# 4_IMU.net
KiCad netlist of a schematic drawn in Altium Designer
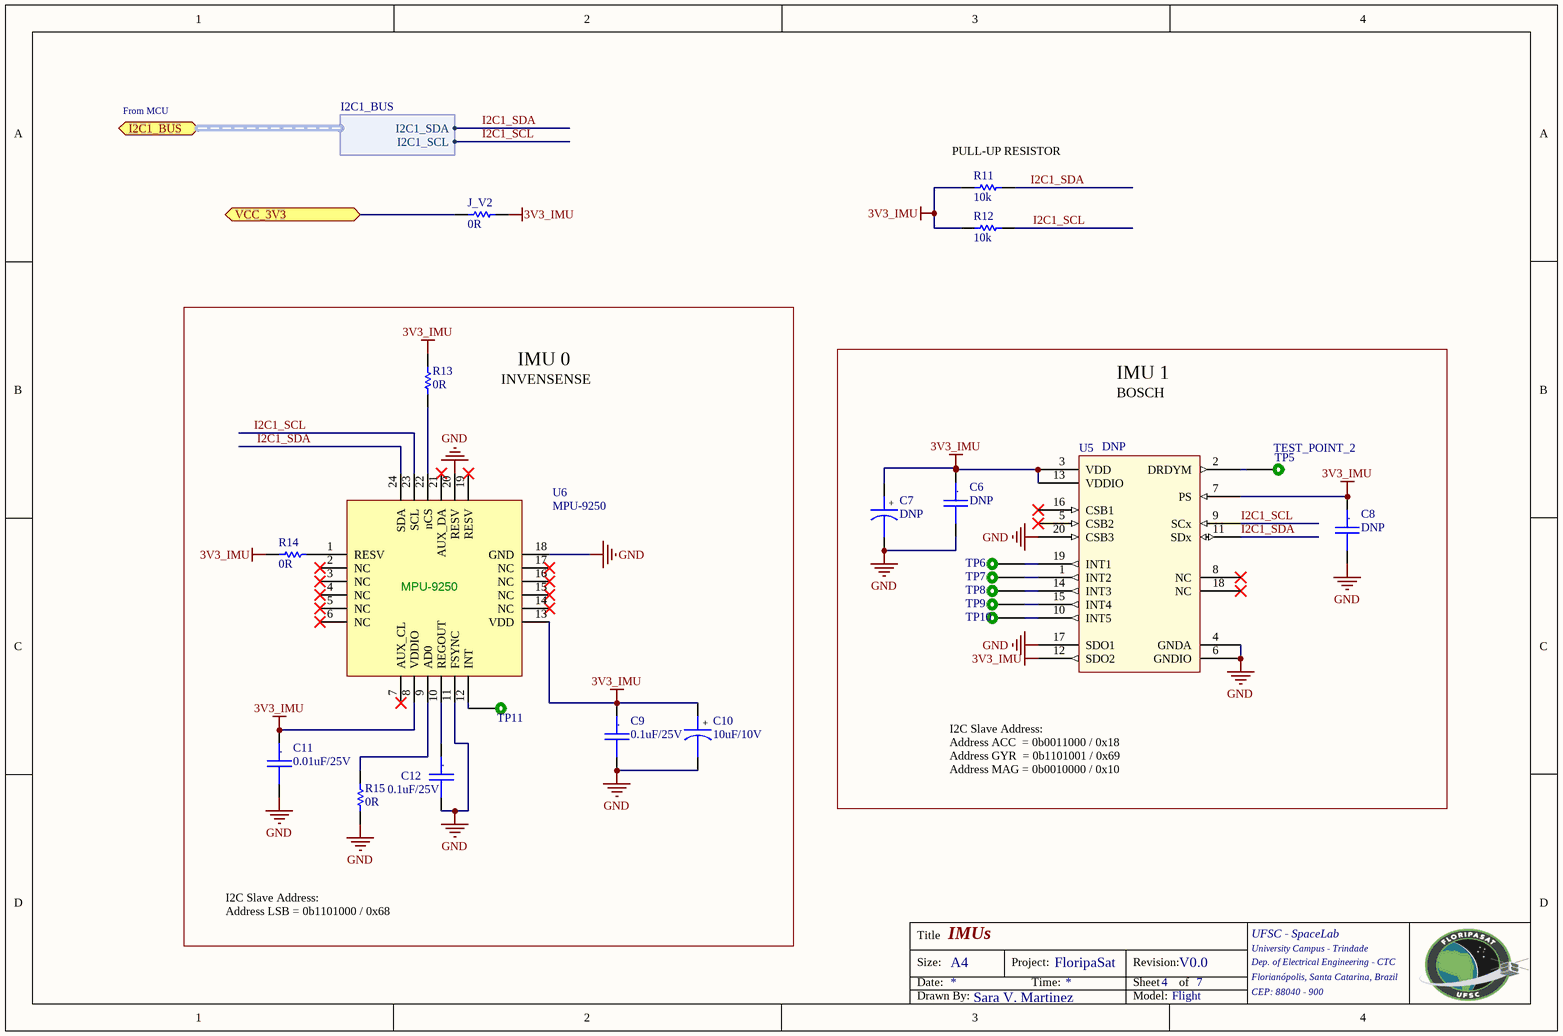
[diagram p0: 4_IMU.SchDoc]

(export (version "E")
  (design (tool "Eeschema 10.0.6"))
  (components
    (comp (ref "C6")
      (value "DNP")
      (footprint "CC0805")
      (description "CAP CER 0.1UF 25V 10% X7R 0805")
      (fields (field (name "PARTNUMBER") "CC0805KRX7R8BB104"))
      (libsource (lib "FloripaSatSchlib") (part "Cap_Cer_X7R_0.1uF_25V_0805"))
    )
    (comp (ref "C7")
      (value "DNP")
      (footprint "FloripaSatPcbLib:CC0805_Tantalum")
      (description "CAP Tantalum 10uF 10V 20% 0805")
      (fields (field (name "PARTNUMBER") "TPSP106M010R2000"))
      (libsource (lib "FloripaSatSchlib") (part "Cap_Tant_SMD_10uF_10V_0805"))
    )
    (comp (ref "C8")
      (value "DNP")
      (footprint "CC0805")
      (description "CAP CER 0.1UF 25V 10% X7R 0805")
      (fields (field (name "PARTNUMBER") "CC0805KRX7R8BB104"))
      (libsource (lib "FloripaSatSchlib") (part "Cap_Cer_X7R_0.1uF_25V_0805"))
    )
    (comp (ref "C9")
      (value "0.1uF/25V")
      (footprint "CC0805")
      (description "CAP CER 0.1UF 25V 10% X7R 0805")
      (fields (field (name "PARTNUMBER") "CC0805KRX7R8BB104"))
      (libsource (lib "FloripaSatSchlib") (part "Cap_Cer_X7R_0.1uF_25V_0805"))
    )
    (comp (ref "C10")
      (value "10uF/10V")
      (footprint "FloripaSatPcbLib:CC0805_Tantalum")
      (description "CAP Tantalum 10uF 10V 20% 0805")
      (fields (field (name "PARTNUMBER") "TPSP106M010R2000"))
      (libsource (lib "FloripaSatSchlib") (part "Cap_Tant_SMD_10uF_10V_0805"))
    )
    (comp (ref "C11")
      (value "0.01uF/25V")
      (footprint "CC0805")
      (description "CAP CER 0.01uF 25V 10% X7R 0805")
      (fields (field (name "PARTNUMBER") "CL21B103KAANNNC"))
      (libsource (lib "FloripaSatSchlib") (part "Cap_Cer_X7R_0.01uF_50V_0805"))
    )
    (comp (ref "C12")
      (value "0.1uF/25V")
      (footprint "CC0805")
      (description "CAP CER 0.1UF 25V 10% X7R 0805")
      (fields (field (name "PARTNUMBER") "CC0805KRX7R8BB104"))
      (libsource (lib "FloripaSatSchlib") (part "Cap_Cer_X7R_0.1uF_25V_0805"))
    )
    (comp (ref "J_V2")
      (value "0R")
      (footprint "FloripaSatPcbLib:0805")
      (description "RES 0R OHM 1/16W JUMPER 0805")
      (fields (field (name "PARTNUMBER") "CRCW08050000Z0EA"))
      (libsource (lib "FloripaSatSchlib") (part "R0R_JUMPER_1/16W_0805"))
    )
    (comp (ref "R11")
      (value "10k")
      (footprint "0805")
      (description "RES 10K OHM 1/8W 1%  0805")
      (fields (field (name "PARTNUMBER") "CRCW080510K0FKEA"))
      (libsource (lib "FloripaSatSchlib") (part "R10k_1%_1/8W_0805"))
    )
    (comp (ref "R12")
      (value "10k")
      (footprint "0805")
      (description "RES 10K OHM 1/8W 1%  0805")
      (fields (field (name "PARTNUMBER") "CRCW080510K0FKEA"))
      (libsource (lib "FloripaSatSchlib") (part "R10k_1%_1/8W_0805"))
    )
    (comp (ref "R13")
      (value "0R")
      (footprint "FloripaSatPcbLib:0805")
      (description "RES 0R OHM 1/16W JUMPER 0805")
      (fields (field (name "PARTNUMBER") "CRCW08050000Z0EA"))
      (libsource (lib "FloripaSatSchlib") (part "R0R_JUMPER_1/16W_0805"))
    )
    (comp (ref "R14")
      (value "0R")
      (footprint "FloripaSatPcbLib:0805")
      (description "RES 0R OHM 1/16W JUMPER 0805")
      (fields (field (name "PARTNUMBER") "CRCW08050000Z0EA"))
      (libsource (lib "FloripaSatSchlib") (part "R0R_JUMPER_1/16W_0805"))
    )
    (comp (ref "R15")
      (value "0R")
      (footprint "FloripaSatPcbLib:0805")
      (description "RES 0R OHM 1/16W JUMPER 0805")
      (fields (field (name "PARTNUMBER") "CRCW08050000Z0EA"))
      (libsource (lib "FloripaSatSchlib") (part "R0R_JUMPER_1/16W_0805"))
    )
    (comp (ref "TP5")
      (value "TEST_POINT_2")
      (footprint "TEST_POINT_2")
      (description "Test point")
      (libsource (lib "FloripaSatSchlib") (part "TEST_POINT_2"))
    )
    (comp (ref "TP6")
      (value "TEST_POINT_2")
      (footprint "TEST_POINT_2")
      (description "Test point")
      (libsource (lib "FloripaSatSchlib") (part "TEST_POINT_2"))
    )
    (comp (ref "TP7")
      (value "TEST_POINT_2")
      (footprint "TEST_POINT_2")
      (description "Test point")
      (libsource (lib "FloripaSatSchlib") (part "TEST_POINT_2"))
    )
    (comp (ref "TP8")
      (value "TEST_POINT_2")
      (footprint "TEST_POINT_2")
      (description "Test point")
      (libsource (lib "FloripaSatSchlib") (part "TEST_POINT_2"))
    )
    (comp (ref "TP9")
      (value "TEST_POINT_2")
      (footprint "TEST_POINT_2")
      (description "Test point")
      (libsource (lib "FloripaSatSchlib") (part "TEST_POINT_2"))
    )
    (comp (ref "TP10")
      (value "TEST_POINT_2")
      (footprint "TEST_POINT_2")
      (description "Test point")
      (libsource (lib "FloripaSatSchlib") (part "TEST_POINT_2"))
    )
    (comp (ref "TP11")
      (value "TEST_POINT_2")
      (footprint "TEST_POINT_2")
      (description "Test point")
      (libsource (lib "FloripaSatSchlib") (part "TEST_POINT_2"))
    )
    (comp (ref "U5") (value "DNP") (footprint "LGA20") (libsource (lib "FloripaSatSchlib") (part "BMX055")))
    (comp (ref "U6")
      (value "MPU-9250")
      (footprint "QFN24P300X300X105-25N")
      (description "SMD Gyroscope/Accelerometer/Magnetometer Sensor; 9-AXIS")
      (libsource (lib "FloripaSatSchlib") (part "MPU9250"))
    )
  )
  (nets
    (net (code "2") (name "/I2C1_SCL") (class "Default")
      (node (ref "R12") (pin "1") (pinfunction "1_1") (pintype "passive"))
      (node (ref "U5") (pin "9") (pinfunction "SCx_9") (pintype "input"))
      (node (ref "U6") (pin "23") (pinfunction "SCL_23") (pintype "passive"))
    )
    (net (code "3") (name "/I2C1_SDA") (class "Default")
      (node (ref "R11") (pin "1") (pinfunction "1_1") (pintype "passive"))
      (node (ref "U5") (pin "11") (pinfunction "SDx_11") (pintype "bidirectional"))
      (node (ref "U6") (pin "24") (pinfunction "SDA_24") (pintype "passive"))
    )
    (net (code "4") (name "/VCC_3V3") (class "Default")
      (node (ref "J_V2") (pin "2") (pinfunction "2_2") (pintype "passive"))
    )
    (net (code "6") (name "3V3_IMU") (class "Default")
      (node (ref "C10") (pin "1") (pinfunction "1_1") (pintype "passive"))
      (node (ref "C11") (pin "1") (pinfunction "1_1") (pintype "passive"))
      (node (ref "C6") (pin "1") (pinfunction "1_1") (pintype "passive"))
      (node (ref "C7") (pin "1") (pinfunction "1_1") (pintype "passive"))
      (node (ref "C8") (pin "1") (pinfunction "1_1") (pintype "passive"))
      (node (ref "C9") (pin "1") (pinfunction "1_1") (pintype "passive"))
      (node (ref "J_V2") (pin "1") (pinfunction "1_1") (pintype "passive"))
      (node (ref "R11") (pin "2") (pinfunction "2_2") (pintype "passive"))
      (node (ref "R12") (pin "2") (pinfunction "2_2") (pintype "passive"))
      (node (ref "R13") (pin "2") (pinfunction "2_2") (pintype "passive"))
      (node (ref "R14") (pin "2") (pinfunction "2_2") (pintype "passive"))
      (node (ref "U5") (pin "12") (pinfunction "SDO2_12") (pintype "output"))
      (node (ref "U5") (pin "13") (pinfunction "VDDIO_13") (pintype "passive"))
      (node (ref "U5") (pin "3") (pinfunction "VDD_3") (pintype "passive"))
      (node (ref "U5") (pin "7") (pinfunction "PS_7") (pintype "input"))
      (node (ref "U6") (pin "13") (pinfunction "VDD_13") (pintype "passive"))
      (node (ref "U6") (pin "8") (pinfunction "VDDIO_8") (pintype "passive"))
    )
    (net (code "7") (name "GND") (class "Default")
      (node (ref "C10") (pin "2") (pinfunction "2_2") (pintype "passive"))
      (node (ref "C11") (pin "2") (pinfunction "2_2") (pintype "passive"))
      (node (ref "C12") (pin "2") (pinfunction "2_2") (pintype "passive"))
      (node (ref "C6") (pin "2") (pinfunction "2_2") (pintype "passive"))
      (node (ref "C7") (pin "2") (pinfunction "2_2") (pintype "passive"))
      (node (ref "C8") (pin "2") (pinfunction "2_2") (pintype "passive"))
      (node (ref "C9") (pin "2") (pinfunction "2_2") (pintype "passive"))
      (node (ref "R15") (pin "2") (pinfunction "2_2") (pintype "passive"))
      (node (ref "U5") (pin "17") (pinfunction "SDO1_17") (pintype "passive"))
      (node (ref "U5") (pin "20") (pinfunction "CSB3_20") (pintype "input"))
      (node (ref "U5") (pin "4") (pinfunction "GNDA_4") (pintype "passive"))
      (node (ref "U5") (pin "6") (pinfunction "GNDIO_6") (pintype "passive"))
      (node (ref "U6") (pin "11") (pinfunction "FSYNC_11") (pintype "passive"))
      (node (ref "U6") (pin "18") (pinfunction "GND_18") (pintype "passive"))
      (node (ref "U6") (pin "20") (pinfunction "RESV_20") (pintype "passive"))
    )
    (net (code "8") (name "Net-(R14-Pad1)") (class "Default")
      (node (ref "R14") (pin "1") (pinfunction "1_1") (pintype "passive"))
      (node (ref "U6") (pin "1") (pinfunction "RESV_1") (pintype "passive"))
    )
    (net (code "9") (name "Net-(U5-DRDYM)") (class "Default")
      (node (ref "TP5") (pin "1") (pinfunction "1_1") (pintype "passive"))
      (node (ref "U5") (pin "2") (pinfunction "DRDYM_2") (pintype "output"))
    )
    (net (code "10") (name "Net-(U5-INT1)") (class "Default")
      (node (ref "TP6") (pin "1") (pinfunction "1_1") (pintype "passive"))
      (node (ref "U5") (pin "19") (pinfunction "INT1_19") (pintype "output"))
    )
    (net (code "11") (name "Net-(U5-INT2)") (class "Default")
      (node (ref "TP7") (pin "1") (pinfunction "1_1") (pintype "passive"))
      (node (ref "U5") (pin "1") (pinfunction "INT2_1") (pintype "output"))
    )
    (net (code "12") (name "Net-(U5-INT3)") (class "Default")
      (node (ref "TP8") (pin "1") (pinfunction "1_1") (pintype "passive"))
      (node (ref "U5") (pin "14") (pinfunction "INT3_14") (pintype "output"))
    )
    (net (code "13") (name "Net-(U5-INT4)") (class "Default")
      (node (ref "TP9") (pin "1") (pinfunction "1_1") (pintype "passive"))
      (node (ref "U5") (pin "15") (pinfunction "INT4_15") (pintype "output"))
    )
    (net (code "14") (name "Net-(U5-INT5)") (class "Default")
      (node (ref "TP10") (pin "1") (pinfunction "1_1") (pintype "passive"))
      (node (ref "U5") (pin "10") (pinfunction "INT5_10") (pintype "output"))
    )
    (net (code "15") (name "Net-(U6-AD0)") (class "Default")
      (node (ref "R15") (pin "1") (pinfunction "1_1") (pintype "passive"))
      (node (ref "U6") (pin "9") (pinfunction "AD0_9") (pintype "passive"))
    )
    (net (code "16") (name "Net-(U6-INT)") (class "Default")
      (node (ref "TP11") (pin "1") (pinfunction "1_1") (pintype "passive"))
      (node (ref "U6") (pin "12") (pinfunction "INT_12") (pintype "passive"))
    )
    (net (code "17") (name "Net-(U6-REGOUT)") (class "Default")
      (node (ref "C12") (pin "1") (pinfunction "1_1") (pintype "passive"))
      (node (ref "U6") (pin "10") (pinfunction "REGOUT_10") (pintype "passive"))
    )
    (net (code "18") (name "Net-(U6-nCS)") (class "Default")
      (node (ref "R13") (pin "1") (pinfunction "1_1") (pintype "passive"))
      (node (ref "U6") (pin "22") (pinfunction "nCS_22") (pintype "passive"))
    )
    (net (code "19") (name "unconnected-(U5-CSB1-Pad16)") (class "Default")
      (node (ref "U5") (pin "16") (pinfunction "CSB1_16") (pintype "input+no_connect"))
    )
    (net (code "20") (name "unconnected-(U5-CSB2-Pad5)") (class "Default")
      (node (ref "U5") (pin "5") (pinfunction "CSB2_5") (pintype "input+no_connect"))
    )
    (net (code "21") (name "unconnected-(U5-NC-Pad8)") (class "Default")
      (node (ref "U5") (pin "8") (pinfunction "NC_8") (pintype "passive+no_connect"))
    )
    (net (code "22") (name "unconnected-(U5-NC-Pad18)") (class "Default")
      (node (ref "U5") (pin "18") (pinfunction "NC_18") (pintype "passive+no_connect"))
    )
    (net (code "23") (name "unconnected-(U6-AUX_CL-Pad7)") (class "Default")
      (node (ref "U6") (pin "7") (pinfunction "AUX_CL_7") (pintype "passive+no_connect"))
    )
    (net (code "24") (name "unconnected-(U6-AUX_DA-Pad21)") (class "Default")
      (node (ref "U6") (pin "21") (pinfunction "AUX_DA_21") (pintype "passive+no_connect"))
    )
    (net (code "25") (name "unconnected-(U6-NC-Pad2)") (class "Default")
      (node (ref "U6") (pin "2") (pinfunction "NC_2") (pintype "passive+no_connect"))
    )
    (net (code "26") (name "unconnected-(U6-NC-Pad3)") (class "Default")
      (node (ref "U6") (pin "3") (pinfunction "NC_3") (pintype "passive+no_connect"))
    )
    (net (code "27") (name "unconnected-(U6-NC-Pad4)") (class "Default")
      (node (ref "U6") (pin "4") (pinfunction "NC_4") (pintype "passive+no_connect"))
    )
    (net (code "28") (name "unconnected-(U6-NC-Pad5)") (class "Default")
      (node (ref "U6") (pin "5") (pinfunction "NC_5") (pintype "passive+no_connect"))
    )
    (net (code "29") (name "unconnected-(U6-NC-Pad6)") (class "Default")
      (node (ref "U6") (pin "6") (pinfunction "NC_6") (pintype "passive+no_connect"))
    )
    (net (code "30") (name "unconnected-(U6-NC-Pad14)") (class "Default")
      (node (ref "U6") (pin "14") (pinfunction "NC_14") (pintype "passive+no_connect"))
    )
    (net (code "31") (name "unconnected-(U6-NC-Pad15)") (class "Default")
      (node (ref "U6") (pin "15") (pinfunction "NC_15") (pintype "passive+no_connect"))
    )
    (net (code "32") (name "unconnected-(U6-NC-Pad16)") (class "Default")
      (node (ref "U6") (pin "16") (pinfunction "NC_16") (pintype "passive+no_connect"))
    )
    (net (code "33") (name "unconnected-(U6-NC-Pad17)") (class "Default")
      (node (ref "U6") (pin "17") (pinfunction "NC_17") (pintype "passive+no_connect"))
    )
    (net (code "34") (name "unconnected-(U6-RESV-Pad19)") (class "Default")
      (node (ref "U6") (pin "19") (pinfunction "RESV_19") (pintype "passive+no_connect"))
    )
  )
)
